# ArduinoUnoShield.net
KiCad netlist of a schematic drawn in Altium Designer
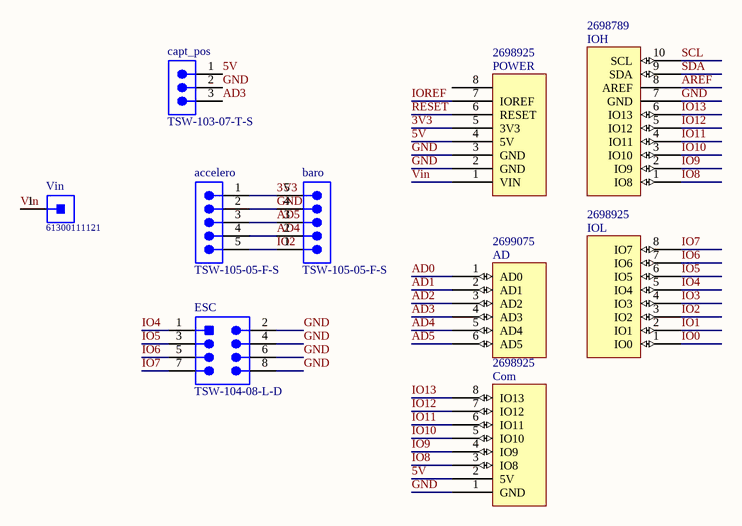
[diagram p0: ArduinoUnoShield.SchDoc]

(export (version "E")
  (design (tool "Eeschema 10.0.6"))
  (components
    (comp (ref "accelero")
      (value "TSW-105-05-F-S")
      (footprint "SMTC-TSW-105-05-X-S")
      (description "0.025\" SQ Post Header, Through-hole, Vertical, -55 to 125 degC, 2.54 mm Pitch, 5-Pin, Male, RoHS")
      (fields (field (name "MANUFACTURER") "Samtec"))
      (libsource (lib "Altium Content Vault") (part "SMTC-TSW-105-05-X-S"))
    )
    (comp (ref "AD")
      (value "AD")
      (footprint "Header:Header 6x1 8.5mm")
      (fields (field (name "SUPPLIER PART NUMBER 4") "2699075"))
      (libsource (lib "Header") (part "AD"))
    )
    (comp (ref "baro")
      (value "TSW-105-05-F-S")
      (footprint "SMTC-TSW-105-05-X-S")
      (description "0.025\" SQ Post Header, Through-hole, Vertical, -55 to 125 degC, 2.54 mm Pitch, 5-Pin, Male, RoHS")
      (fields (field (name "MANUFACTURER") "Samtec"))
      (libsource (lib "Altium Content Vault") (part "SMTC-TSW-105-05-X-S"))
    )
    (comp (ref "capt_pos")
      (value "TSW-103-07-T-S")
      (footprint "SMTC-TSW-103-07-X-S")
      (description "0.025\" SQ Post Header, Through-hole, Vertical, -55 to 105 degC, 2.54 mm Pitch, 3-Pin, Male, RoHS")
      (fields (field (name "MANUFACTURER") "Samtec"))
      (libsource (lib "Altium Content Vault") (part "SMTC-TSW-103-X-X-S-X"))
    )
    (comp (ref "Com")
      (value "POWER_UNO")
      (footprint "Header 8x1 8.5mm")
      (fields (field (name "SUPPLIER PART NUMBER 4") "2698925"))
      (libsource (lib "Header") (part "POWER_UNO"))
    )
    (comp (ref "ESC")
      (value "TSW-104-08-L-D")
      (footprint "SMTC-TSW-104-08-L-D_V")
      (fields (field (name "MANUFACTURER") "Samtec"))
      (libsource (lib "Altium Content Vault") (part "CN-2P-M-R8"))
    )
    (comp (ref "IOH")
      (value "IOH")
      (footprint "Header:Header 10x1 8.5mm")
      (fields (field (name "SUPPLIER PART NUMBER 3") "2698789"))
      (libsource (lib "Header") (part "IOH"))
    )
    (comp (ref "IOL")
      (value "IOL")
      (footprint "Header 8x1 8.5mm")
      (fields (field (name "SUPPLIER PART NUMBER 4") "2698925"))
      (libsource (lib "Header") (part "IOL"))
    )
    (comp (ref "POWER")
      (value "POWER_UNO")
      (footprint "Header 8x1 8.5mm")
      (fields (field (name "SUPPLIER PART NUMBER 4") "2698925"))
      (libsource (lib "Header") (part "POWER_UNO"))
    )
    (comp (ref "Vin")
      (value "61300111121")
      (footprint "61300111121")
      (description "THT Vertical Pin Header WR-PHD, Pitch 2.54 mm, Single Row, 1 pins")
      (fields (field (name "MANUFACTURER") "Wurth Elektronik") (field (name "PUBLISHER") "WurthElektronik"))
      (libsource (lib "Altium Content Vault") (part "WE-CN-1P-M-R1"))
    )
  )
  (nets
    (net (code "1") (name "/3V3") (class "Default")
      (node (ref "POWER") (pin "5") (pinfunction "IO10_5") (pintype "bidirectional"))
      (node (ref "accelero") (pin "1") (pinfunction "1_1") (pintype "passive"))
      (node (ref "baro") (pin "5") (pinfunction "5_5") (pintype "passive"))
    )
    (net (code "2") (name "/5V") (class "Default")
      (node (ref "Com") (pin "2") (pinfunction "5V_2") (pintype "power_in"))
      (node (ref "POWER") (pin "4") (pinfunction "IO9_4") (pintype "bidirectional"))
      (node (ref "capt_pos") (pin "1") (pinfunction "1_1") (pintype "passive"))
    )
    (net (code "3") (name "/AD0") (class "Default")
      (node (ref "AD") (pin "1") (pinfunction "AD0_1") (pintype "bidirectional"))
    )
    (net (code "4") (name "/AD1") (class "Default")
      (node (ref "AD") (pin "2") (pinfunction "AD1_2") (pintype "bidirectional"))
    )
    (net (code "5") (name "/AD2") (class "Default")
      (node (ref "AD") (pin "3") (pinfunction "AD2_3") (pintype "bidirectional"))
    )
    (net (code "6") (name "/AD3") (class "Default")
      (node (ref "AD") (pin "4") (pinfunction "AD3_4") (pintype "bidirectional"))
      (node (ref "capt_pos") (pin "3") (pinfunction "3_3") (pintype "passive"))
    )
    (net (code "7") (name "/AD4") (class "Default")
      (node (ref "AD") (pin "5") (pinfunction "AD4_5") (pintype "bidirectional"))
      (node (ref "accelero") (pin "4") (pinfunction "4_4") (pintype "passive"))
      (node (ref "baro") (pin "2") (pinfunction "2_2") (pintype "passive"))
    )
    (net (code "8") (name "/AD5") (class "Default")
      (node (ref "AD") (pin "6") (pinfunction "AD5_6") (pintype "bidirectional"))
      (node (ref "accelero") (pin "3") (pinfunction "3_3") (pintype "passive"))
      (node (ref "baro") (pin "3") (pinfunction "3_3") (pintype "passive"))
    )
    (net (code "9") (name "/AREF") (class "Default")
      (node (ref "IOH") (pin "8") (pinfunction "AREF_8") (pintype "passive"))
    )
    (net (code "10") (name "/GND") (class "Default")
      (node (ref "Com") (pin "1") (pinfunction "GND_1") (pintype "power_in"))
      (node (ref "ESC") (pin "2") (pinfunction "2_2") (pintype "passive"))
      (node (ref "ESC") (pin "4") (pinfunction "4_4") (pintype "passive"))
      (node (ref "ESC") (pin "6") (pinfunction "6_6") (pintype "passive"))
      (node (ref "ESC") (pin "8") (pinfunction "8_8") (pintype "passive"))
      (node (ref "IOH") (pin "7") (pinfunction "GND_7") (pintype "power_in"))
      (node (ref "POWER") (pin "2") (pinfunction "5V_2") (pintype "power_in"))
      (node (ref "POWER") (pin "3") (pinfunction "IO8_3") (pintype "bidirectional"))
      (node (ref "accelero") (pin "2") (pinfunction "2_2") (pintype "passive"))
      (node (ref "baro") (pin "4") (pinfunction "4_4") (pintype "passive"))
      (node (ref "capt_pos") (pin "2") (pinfunction "2_2") (pintype "passive"))
    )
    (net (code "11") (name "/IO0") (class "Default")
      (node (ref "IOL") (pin "1") (pinfunction "IO0_1") (pintype "bidirectional"))
    )
    (net (code "12") (name "/IO1") (class "Default")
      (node (ref "IOL") (pin "2") (pinfunction "IO1_2") (pintype "bidirectional"))
    )
    (net (code "13") (name "/IO2") (class "Default")
      (node (ref "IOL") (pin "3") (pinfunction "IO2_3") (pintype "bidirectional"))
      (node (ref "accelero") (pin "5") (pinfunction "5_5") (pintype "passive"))
      (node (ref "baro") (pin "1") (pinfunction "1_1") (pintype "passive"))
    )
    (net (code "14") (name "/IO3") (class "Default")
      (node (ref "IOL") (pin "4") (pinfunction "IO3_4") (pintype "bidirectional"))
    )
    (net (code "15") (name "/IO4") (class "Default")
      (node (ref "ESC") (pin "1") (pinfunction "1_1") (pintype "passive"))
      (node (ref "IOL") (pin "5") (pinfunction "IO4_5") (pintype "bidirectional"))
    )
    (net (code "16") (name "/IO5") (class "Default")
      (node (ref "ESC") (pin "3") (pinfunction "3_3") (pintype "passive"))
      (node (ref "IOL") (pin "6") (pinfunction "IO5_6") (pintype "bidirectional"))
    )
    (net (code "17") (name "/IO6") (class "Default")
      (node (ref "ESC") (pin "5") (pinfunction "5_5") (pintype "passive"))
      (node (ref "IOL") (pin "7") (pinfunction "IO6_7") (pintype "bidirectional"))
    )
    (net (code "18") (name "/IO7") (class "Default")
      (node (ref "ESC") (pin "7") (pinfunction "7_7") (pintype "passive"))
      (node (ref "IOL") (pin "8") (pinfunction "IO7_8") (pintype "bidirectional"))
    )
    (net (code "19") (name "/IO8") (class "Default")
      (node (ref "Com") (pin "3") (pinfunction "IO8_3") (pintype "bidirectional"))
      (node (ref "IOH") (pin "1") (pinfunction "IO8_1") (pintype "bidirectional"))
    )
    (net (code "20") (name "/IO9") (class "Default")
      (node (ref "Com") (pin "4") (pinfunction "IO9_4") (pintype "bidirectional"))
      (node (ref "IOH") (pin "2") (pinfunction "IO9_2") (pintype "bidirectional"))
    )
    (net (code "21") (name "/IO10") (class "Default")
      (node (ref "Com") (pin "5") (pinfunction "IO10_5") (pintype "bidirectional"))
      (node (ref "IOH") (pin "3") (pinfunction "IO10_3") (pintype "bidirectional"))
    )
    (net (code "22") (name "/IO11") (class "Default")
      (node (ref "Com") (pin "6") (pinfunction "IO11_6") (pintype "bidirectional"))
      (node (ref "IOH") (pin "4") (pinfunction "IO11_4") (pintype "bidirectional"))
    )
    (net (code "23") (name "/IO12") (class "Default")
      (node (ref "Com") (pin "7") (pinfunction "IO12_7") (pintype "bidirectional"))
      (node (ref "IOH") (pin "5") (pinfunction "IO12_5") (pintype "bidirectional"))
    )
    (net (code "24") (name "/IO13") (class "Default")
      (node (ref "Com") (pin "8") (pinfunction "IO13_8") (pintype "bidirectional"))
      (node (ref "IOH") (pin "6") (pinfunction "IO13_6") (pintype "bidirectional"))
    )
    (net (code "25") (name "/IOREF") (class "Default")
      (node (ref "POWER") (pin "7") (pinfunction "IO12_7") (pintype "bidirectional"))
    )
    (net (code "26") (name "/RESET") (class "Default")
      (node (ref "POWER") (pin "6") (pinfunction "IO11_6") (pintype "bidirectional"))
    )
    (net (code "27") (name "/SCL") (class "Default")
      (node (ref "IOH") (pin "10") (pinfunction "SCL_10") (pintype "bidirectional"))
    )
    (net (code "28") (name "/SDA") (class "Default")
      (node (ref "IOH") (pin "9") (pinfunction "SDA_9") (pintype "bidirectional"))
    )
    (net (code "29") (name "/Vin") (class "Default")
      (node (ref "POWER") (pin "1") (pinfunction "GND_1") (pintype "power_in"))
      (node (ref "Vin") (pin "1") (pinfunction "1_1") (pintype "passive"))
    )
    (net (code "30") (name "unconnected-(POWER-IO13-Pad8)") (class "Default")
      (node (ref "POWER") (pin "8") (pinfunction "IO13_8") (pintype "bidirectional"))
    )
  )
)
